# Port_Controller.net
KiCad netlist of a schematic drawn in Altium Designer
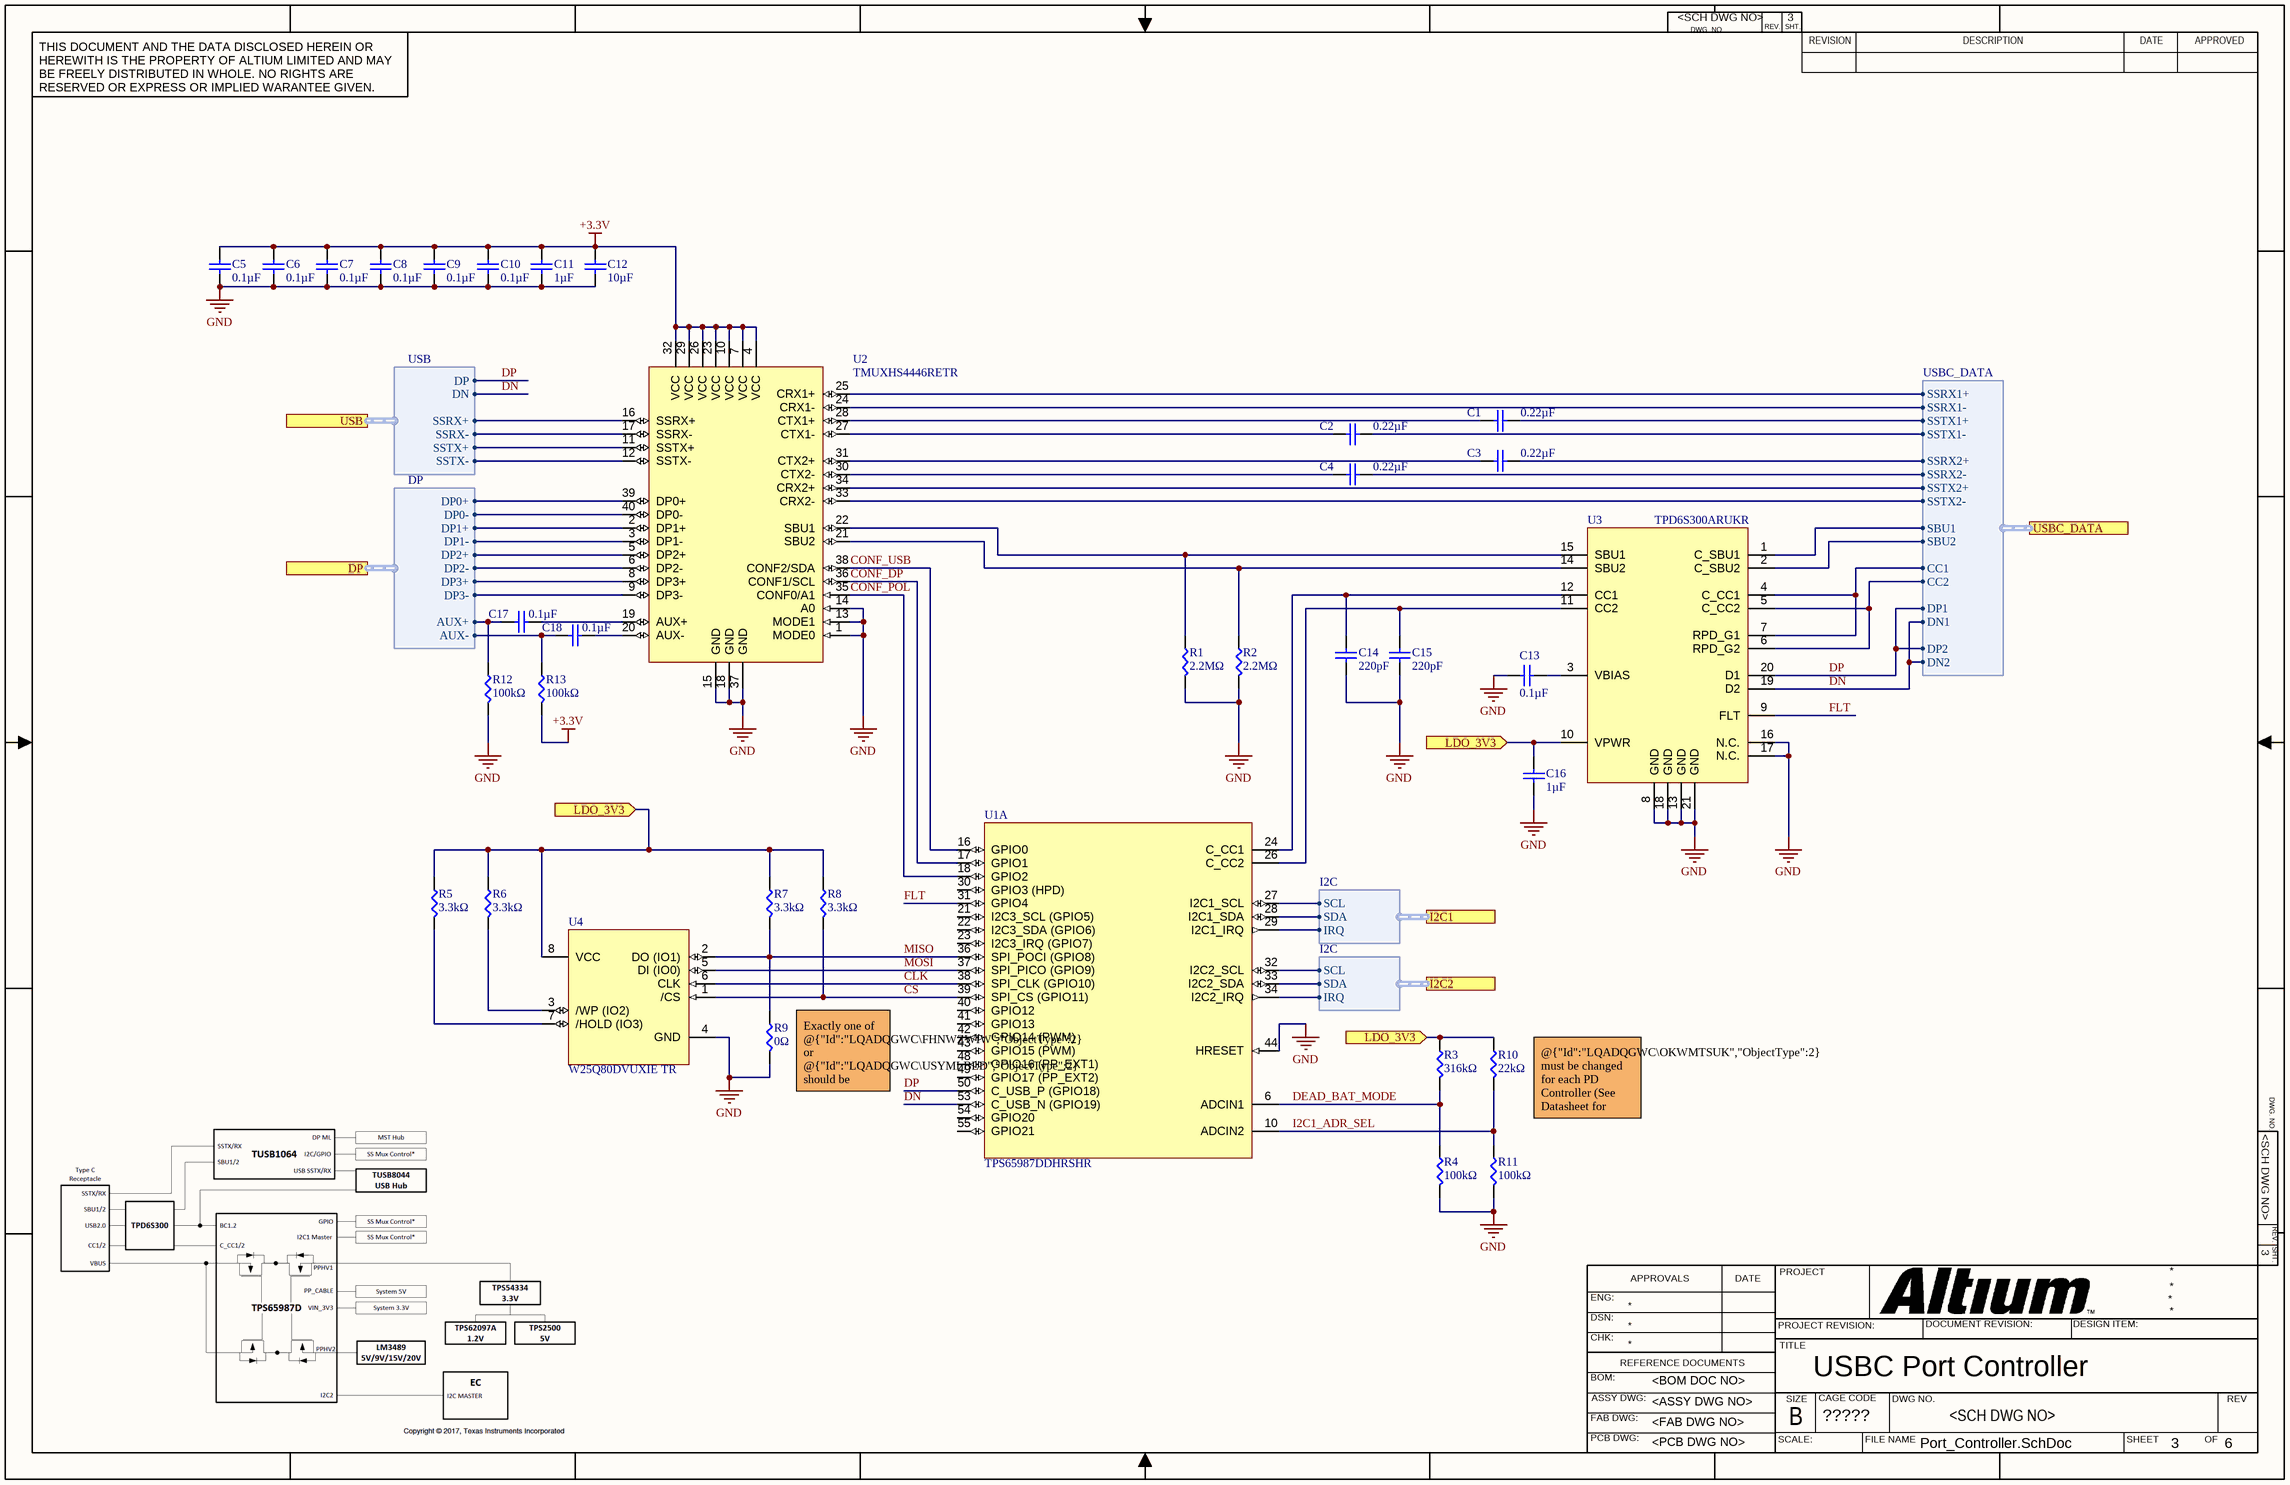
[diagram p0: Port_Controller.SchDoc]

(export (version "E")
  (design (tool "Eeschema 10.0.6"))
  (components
    (comp (ref "C1")
      (value "0.22µF")
      (footprint "CAP0402")
      (description "0.22 µF ±10% 50V Ceramic Capacitor X5R 0402 (1005 Metric)")
      (fields (field (name "VOLTAGE") "50V") (field (name "Comment") "UMK105BJ224KV-F"))
      (libsource (lib "Schlib1") (part "UMK105BJ224KV-F"))
    )
    (comp (ref "C2")
      (value "0.22µF")
      (footprint "CAP0402")
      (description "0.22 µF ±10% 50V Ceramic Capacitor X5R 0402 (1005 Metric)")
      (fields (field (name "VOLTAGE") "50V") (field (name "Comment") "UMK105BJ224KV-F"))
      (libsource (lib "Schlib1") (part "UMK105BJ224KV-F"))
    )
    (comp (ref "C3")
      (value "0.22µF")
      (footprint "CAP0402")
      (description "0.22 µF ±10% 50V Ceramic Capacitor X5R 0402 (1005 Metric)")
      (fields (field (name "VOLTAGE") "50V") (field (name "Comment") "UMK105BJ224KV-F"))
      (libsource (lib "Schlib1") (part "UMK105BJ224KV-F"))
    )
    (comp (ref "C4")
      (value "0.22µF")
      (footprint "CAP0402")
      (description "0.22 µF ±10% 50V Ceramic Capacitor X5R 0402 (1005 Metric)")
      (fields (field (name "VOLTAGE") "50V") (field (name "Comment") "UMK105BJ224KV-F"))
      (libsource (lib "Schlib1") (part "UMK105BJ224KV-F"))
    )
    (comp (ref "C5")
      (value "0.1µF")
      (footprint "CAP0402")
      (description "0.1 µF ±10% 50V Ceramic Capacitor X5R 0402 (1005 Metric)")
      (fields (field (name "VOLTAGE") "50V") (field (name "Comment") "CC0402KRX5R9BB104"))
      (libsource (lib "Schlib1") (part "CC0402KRX5R9BB104"))
    )
    (comp (ref "C6")
      (value "0.1µF")
      (footprint "CAP0402")
      (description "0.1 µF ±10% 50V Ceramic Capacitor X5R 0402 (1005 Metric)")
      (fields (field (name "VOLTAGE") "50V") (field (name "Comment") "CC0402KRX5R9BB104"))
      (libsource (lib "Schlib1") (part "CC0402KRX5R9BB104"))
    )
    (comp (ref "C7")
      (value "0.1µF")
      (footprint "CAP0402")
      (description "0.1 µF ±10% 50V Ceramic Capacitor X5R 0402 (1005 Metric)")
      (fields (field (name "VOLTAGE") "50V") (field (name "Comment") "CC0402KRX5R9BB104"))
      (libsource (lib "Schlib1") (part "CC0402KRX5R9BB104"))
    )
    (comp (ref "C8")
      (value "0.1µF")
      (footprint "CAP0402")
      (description "0.1 µF ±10% 50V Ceramic Capacitor X5R 0402 (1005 Metric)")
      (fields (field (name "VOLTAGE") "50V") (field (name "Comment") "CC0402KRX5R9BB104"))
      (libsource (lib "Schlib1") (part "CC0402KRX5R9BB104"))
    )
    (comp (ref "C9")
      (value "0.1µF")
      (footprint "CAP0402")
      (description "0.1 µF ±10% 50V Ceramic Capacitor X5R 0402 (1005 Metric)")
      (fields (field (name "VOLTAGE") "50V") (field (name "Comment") "CC0402KRX5R9BB104"))
      (libsource (lib "Schlib1") (part "CC0402KRX5R9BB104"))
    )
    (comp (ref "C10")
      (value "0.1µF")
      (footprint "CAP0402")
      (description "0.1 µF ±10% 50V Ceramic Capacitor X5R 0402 (1005 Metric)")
      (fields (field (name "VOLTAGE") "50V") (field (name "Comment") "CC0402KRX5R9BB104"))
      (libsource (lib "Schlib1") (part "CC0402KRX5R9BB104"))
    )
    (comp (ref "C11")
      (value "1µF")
      (footprint "CAP0402")
      (description "1 µF ±10% 50V Ceramic Capacitor X5R 0402 (1005 Metric)")
      (fields (field (name "VOLTAGE") "50V") (field (name "Comment") "GRM155R61H105KE05D"))
      (libsource (lib "Schlib1") (part "GRM155R61H105KE05D"))
    )
    (comp (ref "C12")
      (value "10µF")
      (footprint "CAP0402")
      (description "10 µF ±20% 6.3V Ceramic Capacitor X5R 0402 (1005 Metric)")
      (fields (field (name "VOLTAGE") "6.3V") (field (name "Comment") "CL05A106MQ5NUNC"))
      (libsource (lib "Schlib1") (part "CL05A106MQ5NUNC"))
    )
    (comp (ref "C13")
      (value "0.1µF")
      (footprint "CAP0402")
      (description "0.1 µF ±10% 50V Ceramic Capacitor X5R 0402 (1005 Metric)")
      (fields (field (name "VOLTAGE") "50V") (field (name "Comment") "CC0402KRX5R9BB104"))
      (libsource (lib "Schlib1") (part "CC0402KRX5R9BB104"))
    )
    (comp (ref "C14")
      (value "220pF")
      (footprint "CAP0402")
      (description "220 pF ±5% 50V Ceramic Capacitor C0G, NP0 0402 (1005 Metric)")
      (fields (field (name "VOLTAGE") "50V") (field (name "Comment") "GRM1555C1H221JA01D"))
      (libsource (lib "Schlib1") (part "GRM1555C1H221JA01D"))
    )
    (comp (ref "C15")
      (value "220pF")
      (footprint "CAP0402")
      (description "220 pF ±5% 50V Ceramic Capacitor C0G, NP0 0402 (1005 Metric)")
      (fields (field (name "VOLTAGE") "50V") (field (name "Comment") "GRM1555C1H221JA01D"))
      (libsource (lib "Schlib1") (part "GRM1555C1H221JA01D"))
    )
    (comp (ref "C16")
      (value "1µF")
      (footprint "CAP0402")
      (description "1 µF ±10% 50V Ceramic Capacitor X5R 0402 (1005 Metric)")
      (fields (field (name "VOLTAGE") "50V") (field (name "Comment") "GRM155R61H105KE05D"))
      (libsource (lib "Schlib1") (part "GRM155R61H105KE05D"))
    )
    (comp (ref "C17")
      (value "0.1µF")
      (footprint "CAP0402")
      (description "0.1 µF ±10% 50V Ceramic Capacitor X5R 0402 (1005 Metric)")
      (fields (field (name "VOLTAGE") "50V") (field (name "Comment") "CC0402KRX5R9BB104"))
      (libsource (lib "Schlib1") (part "CC0402KRX5R9BB104"))
    )
    (comp (ref "C18")
      (value "0.1µF")
      (footprint "CAP0402")
      (description "0.1 µF ±10% 50V Ceramic Capacitor X5R 0402 (1005 Metric)")
      (fields (field (name "VOLTAGE") "50V") (field (name "Comment") "CC0402KRX5R9BB104"))
      (libsource (lib "Schlib1") (part "CC0402KRX5R9BB104"))
    )
    (comp (ref "R1")
      (value "2.2MΩ")
      (footprint "RES0402")
      (description "2.2 MOhms ±1% 0.063W, 1/16W Chip Resistor 0402 (1005 Metric) Moisture Resistant Thick Film")
      (fields (field (name "Comment") "RC0402FR-072M2L"))
      (libsource (lib "Schlib1") (part "RC0402FR-072M2L"))
    )
    (comp (ref "R2")
      (value "2.2MΩ")
      (footprint "RES0402")
      (description "2.2 MOhms ±1% 0.063W, 1/16W Chip Resistor 0402 (1005 Metric) Moisture Resistant Thick Film")
      (fields (field (name "Comment") "RC0402FR-072M2L"))
      (libsource (lib "Schlib1") (part "RC0402FR-072M2L"))
    )
    (comp (ref "R3")
      (value "316kΩ")
      (footprint "RES0402")
      (description "316 kOhms ±1% 0.1W, 1/10W Chip Resistor 0402 (1005 Metric) Automotive AEC-Q200 Thick Film")
      (fields (field (name "Comment") "CRCW0402316KFKED"))
      (libsource (lib "Schlib1") (part "CRCW0402316KFKED"))
    )
    (comp (ref "R4")
      (value "100kΩ")
      (footprint "RES0402")
      (description "100 kOhms ±1% 0.1W, 1/10W Chip Resistor 0402 (1005 Metric) Automotive AEC-Q200 Thick Film")
      (fields (field (name "Comment") "ERJ-2RKF1003X"))
      (libsource (lib "Schlib1") (part "ERJ-2RKF1003X"))
    )
    (comp (ref "R5")
      (value "3.3kΩ")
      (footprint "RES0402")
      (description "3.3 kOhms ±0.1% 0.063W, 1/16W Chip Resistor 0402 (1005 Metric) Automotive AEC-Q200 Thin Film")
      (fields (field (name "Comment") "ERA-2AEB332X"))
      (libsource (lib "Schlib1") (part "ERA-2AEB332X"))
    )
    (comp (ref "R6")
      (value "3.3kΩ")
      (footprint "RES0402")
      (description "3.3 kOhms ±0.1% 0.063W, 1/16W Chip Resistor 0402 (1005 Metric) Automotive AEC-Q200 Thin Film")
      (fields (field (name "Comment") "ERA-2AEB332X"))
      (libsource (lib "Schlib1") (part "ERA-2AEB332X"))
    )
    (comp (ref "R7")
      (value "3.3kΩ")
      (footprint "RES0402")
      (description "3.3 kOhms ±0.1% 0.063W, 1/16W Chip Resistor 0402 (1005 Metric) Automotive AEC-Q200 Thin Film")
      (fields (field (name "Comment") "ERA-2AEB332X"))
      (libsource (lib "Schlib1") (part "ERA-2AEB332X"))
    )
    (comp (ref "R8")
      (value "3.3kΩ")
      (footprint "RES0402")
      (description "3.3 kOhms ±0.1% 0.063W, 1/16W Chip Resistor 0402 (1005 Metric) Automotive AEC-Q200 Thin Film")
      (fields (field (name "Comment") "ERA-2AEB332X"))
      (libsource (lib "Schlib1") (part "ERA-2AEB332X"))
    )
    (comp (ref "R9")
      (value "0Ω")
      (footprint "RES0402")
      (description "0 Ohms Jumper Chip Resistor 0402 (1005 Metric) Moisture Resistant Thick Film")
      (fields (field (name "Comment") "RC0402JR-070RL"))
      (libsource (lib "Schlib1") (part "RC0402JR-070RL"))
    )
    (comp (ref "R10")
      (value "22kΩ")
      (footprint "RES0402")
      (description "22 kOhms ±1% 0.1W, 1/10W Chip Resistor 0402 (1005 Metric) Automotive AEC-Q200 Thick Film")
      (fields (field (name "Comment") "ERJ-2RKF2202X"))
      (libsource (lib "Schlib1") (part "ERJ-2RKF2202X"))
    )
    (comp (ref "R11")
      (value "100kΩ")
      (footprint "RES0402")
      (description "100 kOhms ±1% 0.1W, 1/10W Chip Resistor 0402 (1005 Metric) Automotive AEC-Q200 Thick Film")
      (fields (field (name "Comment") "ERJ-2RKF1003X"))
      (libsource (lib "Schlib1") (part "ERJ-2RKF1003X"))
    )
    (comp (ref "R12")
      (value "100kΩ")
      (footprint "RES0402")
      (description "100 kOhms ±1% 0.1W, 1/10W Chip Resistor 0402 (1005 Metric) Automotive AEC-Q200 Thick Film")
      (fields (field (name "Comment") "ERJ-2RKF1003X"))
      (libsource (lib "Schlib1") (part "ERJ-2RKF1003X"))
    )
    (comp (ref "R13")
      (value "100kΩ")
      (footprint "RES0402")
      (description "100 kOhms ±1% 0.1W, 1/10W Chip Resistor 0402 (1005 Metric) Automotive AEC-Q200 Thick Film")
      (fields (field (name "Comment") "ERJ-2RKF1003X"))
      (libsource (lib "Schlib1") (part "ERJ-2RKF1003X"))
    )
    (comp (ref "U1")
      (value "TPS65987DDHRSHR")
      (footprint "56-VQFN (7x7)")
      (description "USB, Type-C Controller PMIC 56-VQFN (7x7)")
      (fields (field (name "MANUFACTURER") "Texas Instruments"))
      (libsource (lib "Schlib1") (part "TPS65987DDHRSHR"))
    )
    (comp (ref "U2")
      (value "TMUXHS4446RETR")
      (description "4 Circuit IC Switch 4:4 7Ohm (Typ) 40-WQFN (6x3)")
      (fields (field (name "MANUFACTURER") "Texas Instruments"))
      (libsource (lib "Schlib1") (part "TMUXHS4446RETR"))
    )
    (comp (ref "U3")
      (value "TPD6S300ARUKR")
      (description "Overvoltage/Surge Protection IC 8V Internal Switch 20-WQFN (3x3)")
      (fields (field (name "MANUFACTURER") "Texas Instruments"))
      (libsource (lib "Schlib1") (part "TPD6S300ARUKR"))
    )
    (comp (ref "U4")
      (value "W25Q80DVUXIE TR")
      (description "FLASH - NOR Memory IC 8Mbit SPI - Quad I/O 104 MHz 8-USON (2x3)")
      (fields (field (name "MANUFACTURER") "Winbond Electronics"))
      (libsource (lib "Schlib1") (part "W25Q80DVUXIE TR"))
    )
  )
  (nets
    (net (code "4") (name "+3.3V") (class "Default")
      (node (ref "C10") (pin "2") (pinfunction "2_2") (pintype "passive"))
      (node (ref "C11") (pin "2") (pinfunction "2_2") (pintype "passive"))
      (node (ref "C12") (pin "2") (pinfunction "2_2") (pintype "passive"))
      (node (ref "C5") (pin "2") (pinfunction "2_2") (pintype "passive"))
      (node (ref "C6") (pin "2") (pinfunction "2_2") (pintype "passive"))
      (node (ref "C7") (pin "2") (pinfunction "2_2") (pintype "passive"))
      (node (ref "C8") (pin "2") (pinfunction "2_2") (pintype "passive"))
      (node (ref "C9") (pin "2") (pinfunction "2_2") (pintype "passive"))
      (node (ref "R13") (pin "1") (pinfunction "1_1") (pintype "passive"))
      (node (ref "U2") (pin "10") (pinfunction "VCC_10") (pintype "passive"))
      (node (ref "U2") (pin "23") (pinfunction "VCC_23") (pintype "passive"))
      (node (ref "U2") (pin "26") (pinfunction "VCC_26") (pintype "passive"))
      (node (ref "U2") (pin "29") (pinfunction "VCC_29") (pintype "passive"))
      (node (ref "U2") (pin "32") (pinfunction "VCC_32") (pintype "passive"))
      (node (ref "U2") (pin "4") (pinfunction "VCC_4") (pintype "passive"))
      (node (ref "U2") (pin "7") (pinfunction "VCC_7") (pintype "passive"))
    )
    (net (code "5") (name "/AUX+") (class "Default")
      (node (ref "C17") (pin "1") (pinfunction "1_1") (pintype "passive"))
      (node (ref "R12") (pin "2") (pinfunction "2_2") (pintype "passive"))
    )
    (net (code "6") (name "/AUX-") (class "Default")
      (node (ref "C18") (pin "1") (pinfunction "1_1") (pintype "passive"))
      (node (ref "R13") (pin "2") (pinfunction "2_2") (pintype "passive"))
    )
    (net (code "7") (name "/CC1") (class "Default")
      (node (ref "U3") (pin "4") (pinfunction "C_CC1_4") (pintype "passive"))
      (node (ref "U3") (pin "7") (pinfunction "RPD_G1_7") (pintype "passive"))
    )
    (net (code "8") (name "/CC2") (class "Default")
      (node (ref "U3") (pin "5") (pinfunction "C_CC2_5") (pintype "passive"))
      (node (ref "U3") (pin "6") (pinfunction "RPD_G2_6") (pintype "passive"))
    )
    (net (code "9") (name "/CLK") (class "Default")
      (node (ref "U1") (pin "38") (pinfunction "SPI_CLK_(GPIO10)_38") (pintype "bidirectional"))
      (node (ref "U4") (pin "6") (pinfunction "CLK_6") (pintype "input"))
    )
    (net (code "10") (name "/CONF_DP") (class "Default")
      (node (ref "U1") (pin "17") (pinfunction "GPIO1_17") (pintype "bidirectional"))
      (node (ref "U2") (pin "36") (pinfunction "CONF1/SCL_36") (pintype "bidirectional"))
    )
    (net (code "11") (name "/CONF_POL") (class "Default")
      (node (ref "U1") (pin "18") (pinfunction "GPIO2_18") (pintype "bidirectional"))
      (node (ref "U2") (pin "35") (pinfunction "CONF0/A1_35") (pintype "input"))
    )
    (net (code "12") (name "/CONF_USB") (class "Default")
      (node (ref "U1") (pin "16") (pinfunction "GPIO0_16") (pintype "bidirectional"))
      (node (ref "U2") (pin "38") (pinfunction "CONF2/SDA_38") (pintype "bidirectional"))
    )
    (net (code "13") (name "/CS") (class "Default")
      (node (ref "R8") (pin "1") (pinfunction "1_1") (pintype "passive"))
      (node (ref "U1") (pin "39") (pinfunction "SPI_CS_(GPIO11)_39") (pintype "bidirectional"))
      (node (ref "U4") (pin "1") (pinfunction "/CS_1") (pintype "input"))
    )
    (net (code "14") (name "/DEAD_BAT_MODE") (class "Default")
      (node (ref "R3") (pin "1") (pinfunction "1_1") (pintype "passive"))
      (node (ref "R4") (pin "2") (pinfunction "2_2") (pintype "passive"))
      (node (ref "U1") (pin "6") (pinfunction "ADCIN1_6") (pintype "passive"))
    )
    (net (code "15") (name "/DN") (class "Default")
      (node (ref "U1") (pin "53") (pinfunction "C_USB_N_(GPIO19)_53") (pintype "bidirectional"))
      (node (ref "U3") (pin "19") (pinfunction "D2_19") (pintype "passive"))
    )
    (net (code "16") (name "/DP") (class "Default")
      (node (ref "U1") (pin "50") (pinfunction "C_USB_P_(GPIO18)_50") (pintype "bidirectional"))
      (node (ref "U3") (pin "20") (pinfunction "D1_20") (pintype "passive"))
    )
    (net (code "17") (name "/DP0+") (class "Default")
      (node (ref "U2") (pin "39") (pinfunction "DP0+_39") (pintype "bidirectional"))
    )
    (net (code "18") (name "/DP0-") (class "Default")
      (node (ref "U2") (pin "40") (pinfunction "DP0-_40") (pintype "bidirectional"))
    )
    (net (code "19") (name "/DP1+") (class "Default")
      (node (ref "U2") (pin "2") (pinfunction "DP1+_2") (pintype "bidirectional"))
    )
    (net (code "20") (name "/DP1-") (class "Default")
      (node (ref "U2") (pin "3") (pinfunction "DP1-_3") (pintype "bidirectional"))
    )
    (net (code "21") (name "/DP2+") (class "Default")
      (node (ref "U2") (pin "5") (pinfunction "DP2+_5") (pintype "bidirectional"))
    )
    (net (code "22") (name "/DP2-") (class "Default")
      (node (ref "U2") (pin "6") (pinfunction "DP2-_6") (pintype "bidirectional"))
    )
    (net (code "23") (name "/DP3+") (class "Default")
      (node (ref "U2") (pin "8") (pinfunction "DP3+_8") (pintype "bidirectional"))
    )
    (net (code "24") (name "/DP3-") (class "Default")
      (node (ref "U2") (pin "9") (pinfunction "DP3-_9") (pintype "bidirectional"))
    )
    (net (code "25") (name "/FLT") (class "Default")
      (node (ref "U1") (pin "31") (pinfunction "GPIO4_31") (pintype "bidirectional"))
      (node (ref "U3") (pin "9") (pinfunction "FLT_9") (pintype "passive"))
    )
    (net (code "26") (name "/I2C1_ADR_SEL") (class "Default")
      (node (ref "R10") (pin "1") (pinfunction "1_1") (pintype "passive"))
      (node (ref "R11") (pin "2") (pinfunction "2_2") (pintype "passive"))
      (node (ref "U1") (pin "10") (pinfunction "ADCIN2_10") (pintype "passive"))
    )
    (net (code "27") (name "/LDO_3V3") (class "Default")
      (node (ref "C16") (pin "2") (pinfunction "2_2") (pintype "passive"))
      (node (ref "R10") (pin "2") (pinfunction "2_2") (pintype "passive"))
      (node (ref "R3") (pin "2") (pinfunction "2_2") (pintype "passive"))
      (node (ref "R5") (pin "2") (pinfunction "2_2") (pintype "passive"))
      (node (ref "R6") (pin "2") (pinfunction "2_2") (pintype "passive"))
      (node (ref "R7") (pin "2") (pinfunction "2_2") (pintype "passive"))
      (node (ref "R8") (pin "2") (pinfunction "2_2") (pintype "passive"))
      (node (ref "U3") (pin "10") (pinfunction "VPWR_10") (pintype "passive"))
      (node (ref "U4") (pin "8") (pinfunction "VCC_8") (pintype "passive"))
    )
    (net (code "28") (name "/MISO") (class "Default")
      (node (ref "R7") (pin "1") (pinfunction "1_1") (pintype "passive"))
      (node (ref "R9") (pin "2") (pinfunction "2_2") (pintype "passive"))
      (node (ref "U1") (pin "36") (pinfunction "SPI_POCI_(GPIO8)_36") (pintype "bidirectional"))
      (node (ref "U4") (pin "2") (pinfunction "DO_(IO1)_2") (pintype "bidirectional"))
    )
    (net (code "29") (name "/MOSI") (class "Default")
      (node (ref "U1") (pin "37") (pinfunction "SPI_PICO_(GPIO9)_37") (pintype "bidirectional"))
      (node (ref "U4") (pin "5") (pinfunction "DI_(IO0)_5") (pintype "bidirectional"))
    )
    (net (code "30") (name "/SBU1") (class "Default")
      (node (ref "U3") (pin "1") (pinfunction "C_SBU1_1") (pintype "passive"))
    )
    (net (code "31") (name "/SBU2") (class "Default")
      (node (ref "U3") (pin "2") (pinfunction "C_SBU2_2") (pintype "passive"))
    )
    (net (code "32") (name "/SSRX+") (class "Default")
      (node (ref "U2") (pin "16") (pinfunction "SSRX+_16") (pintype "bidirectional"))
    )
    (net (code "33") (name "/SSRX-") (class "Default")
      (node (ref "U2") (pin "17") (pinfunction "SSRX-_17") (pintype "bidirectional"))
    )
    (net (code "34") (name "/SSRX1+") (class "Default")
      (node (ref "U2") (pin "25") (pinfunction "CRX1+_25") (pintype "bidirectional"))
    )
    (net (code "35") (name "/SSRX1-") (class "Default")
      (node (ref "U2") (pin "24") (pinfunction "CRX1-_24") (pintype "bidirectional"))
    )
    (net (code "36") (name "/SSRX2+") (class "Default")
      (node (ref "C3") (pin "2") (pinfunction "2_2") (pintype "passive"))
    )
    (net (code "37") (name "/SSRX2-") (class "Default")
      (node (ref "C4") (pin "2") (pinfunction "2_2") (pintype "passive"))
    )
    (net (code "38") (name "/SSTX+") (class "Default")
      (node (ref "U2") (pin "11") (pinfunction "SSTX+_11") (pintype "bidirectional"))
    )
    (net (code "39") (name "/SSTX-") (class "Default")
      (node (ref "U2") (pin "12") (pinfunction "SSTX-_12") (pintype "bidirectional"))
    )
    (net (code "40") (name "/SSTX1+") (class "Default")
      (node (ref "C1") (pin "2") (pinfunction "2_2") (pintype "passive"))
    )
    (net (code "41") (name "/SSTX1-") (class "Default")
      (node (ref "C2") (pin "2") (pinfunction "2_2") (pintype "passive"))
    )
    (net (code "42") (name "/SSTX2+") (class "Default")
      (node (ref "U2") (pin "34") (pinfunction "CRX2+_34") (pintype "bidirectional"))
    )
    (net (code "43") (name "/SSTX2-") (class "Default")
      (node (ref "U2") (pin "33") (pinfunction "CRX2-_33") (pintype "bidirectional"))
    )
    (net (code "48") (name "GND") (class "Default")
      (node (ref "C10") (pin "1") (pinfunction "1_1") (pintype "passive"))
      (node (ref "C11") (pin "1") (pinfunction "1_1") (pintype "passive"))
      (node (ref "C12") (pin "1") (pinfunction "1_1") (pintype "passive"))
      (node (ref "C13") (pin "1") (pinfunction "1_1") (pintype "passive"))
      (node (ref "C14") (pin "1") (pinfunction "1_1") (pintype "passive"))
      (node (ref "C15") (pin "1") (pinfunction "1_1") (pintype "passive"))
      (node (ref "C16") (pin "1") (pinfunction "1_1") (pintype "passive"))
      (node (ref "C5") (pin "1") (pinfunction "1_1") (pintype "passive"))
      (node (ref "C6") (pin "1") (pinfunction "1_1") (pintype "passive"))
      (node (ref "C7") (pin "1") (pinfunction "1_1") (pintype "passive"))
      (node (ref "C8") (pin "1") (pinfunction "1_1") (pintype "passive"))
      (node (ref "C9") (pin "1") (pinfunction "1_1") (pintype "passive"))
      (node (ref "R1") (pin "1") (pinfunction "1_1") (pintype "passive"))
      (node (ref "R11") (pin "1") (pinfunction "1_1") (pintype "passive"))
      (node (ref "R12") (pin "1") (pinfunction "1_1") (pintype "passive"))
      (node (ref "R2") (pin "1") (pinfunction "1_1") (pintype "passive"))
      (node (ref "R4") (pin "1") (pinfunction "1_1") (pintype "passive"))
      (node (ref "R9") (pin "1") (pinfunction "1_1") (pintype "passive"))
      (node (ref "U1") (pin "44") (pinfunction "HRESET_44") (pintype "input"))
      (node (ref "U2") (pin "1") (pinfunction "MODE0_1") (pintype "input"))
      (node (ref "U2") (pin "13") (pinfunction "MODE1_13") (pintype "input"))
      (node (ref "U2") (pin "14") (pinfunction "A0_14") (pintype "input"))
      (node (ref "U2") (pin "15") (pinfunction "GND_15") (pintype "passive"))
      (node (ref "U2") (pin "18") (pinfunction "GND_18") (pintype "passive"))
      (node (ref "U2") (pin "37") (pinfunction "GND_37") (pintype "passive"))
      (node (ref "U3") (pin "13") (pinfunction "GND_13") (pintype "passive"))
      (node (ref "U3") (pin "16") (pinfunction "N.C._16") (pintype "passive"))
      (node (ref "U3") (pin "17") (pinfunction "N.C._17") (pintype "passive"))
      (node (ref "U3") (pin "18") (pinfunction "GND_18") (pintype "passive"))
      (node (ref "U3") (pin "21") (pinfunction "GND_21") (pintype "passive"))
      (node (ref "U3") (pin "8") (pinfunction "GND_8") (pintype "passive"))
      (node (ref "U4") (pin "4") (pinfunction "GND_4") (pintype "passive"))
    )
    (net (code "49") (name "Net-(U1A-C_CC1)") (class "Default")
      (node (ref "C14") (pin "2") (pinfunction "2_2") (pintype "passive"))
      (node (ref "U1") (pin "24") (pinfunction "C_CC1_24") (pintype "passive"))
      (node (ref "U3") (pin "12") (pinfunction "CC1_12") (pintype "passive"))
    )
    (net (code "50") (name "Net-(U1A-C_CC2)") (class "Default")
      (node (ref "C15") (pin "2") (pinfunction "2_2") (pintype "passive"))
      (node (ref "U1") (pin "26") (pinfunction "C_CC2_26") (pintype "passive"))
      (node (ref "U3") (pin "11") (pinfunction "CC2_11") (pintype "passive"))
    )
    (net (code "51") (name "Net-(U2-AUX+)") (class "Default")
      (node (ref "C17") (pin "2") (pinfunction "2_2") (pintype "passive"))
      (node (ref "U2") (pin "19") (pinfunction "AUX+_19") (pintype "bidirectional"))
    )
    (net (code "52") (name "Net-(U2-AUX-)") (class "Default")
      (node (ref "C18") (pin "2") (pinfunction "2_2") (pintype "passive"))
      (node (ref "U2") (pin "20") (pinfunction "AUX-_20") (pintype "bidirectional"))
    )
    (net (code "53") (name "Net-(U2-CTX1+)") (class "Default")
      (node (ref "C1") (pin "1") (pinfunction "1_1") (pintype "passive"))
      (node (ref "U2") (pin "28") (pinfunction "CTX1+_28") (pintype "bidirectional"))
    )
    (net (code "54") (name "Net-(U2-CTX1-)") (class "Default")
      (node (ref "C2") (pin "1") (pinfunction "1_1") (pintype "passive"))
      (node (ref "U2") (pin "27") (pinfunction "CTX1-_27") (pintype "bidirectional"))
    )
    (net (code "55") (name "Net-(U2-CTX2+)") (class "Default")
      (node (ref "C3") (pin "1") (pinfunction "1_1") (pintype "passive"))
      (node (ref "U2") (pin "31") (pinfunction "CTX2+_31") (pintype "bidirectional"))
    )
    (net (code "56") (name "Net-(U2-CTX2-)") (class "Default")
      (node (ref "C4") (pin "1") (pinfunction "1_1") (pintype "passive"))
      (node (ref "U2") (pin "30") (pinfunction "CTX2-_30") (pintype "bidirectional"))
    )
    (net (code "57") (name "Net-(U2-SBU1)") (class "Default")
      (node (ref "R1") (pin "2") (pinfunction "2_2") (pintype "passive"))
      (node (ref "U2") (pin "22") (pinfunction "SBU1_22") (pintype "bidirectional"))
      (node (ref "U3") (pin "15") (pinfunction "SBU1_15") (pintype "passive"))
    )
    (net (code "58") (name "Net-(U2-SBU2)") (class "Default")
      (node (ref "R2") (pin "2") (pinfunction "2_2") (pintype "passive"))
      (node (ref "U2") (pin "21") (pinfunction "SBU2_21") (pintype "bidirectional"))
      (node (ref "U3") (pin "14") (pinfunction "SBU2_14") (pintype "passive"))
    )
    (net (code "59") (name "Net-(U3-VBIAS)") (class "Default")
      (node (ref "C13") (pin "2") (pinfunction "2_2") (pintype "passive"))
      (node (ref "U3") (pin "3") (pinfunction "VBIAS_3") (pintype "passive"))
    )
    (net (code "60") (name "Net-(U4-{slash}HOLD_(IO3))") (class "Default")
      (node (ref "R5") (pin "1") (pinfunction "1_1") (pintype "passive"))
      (node (ref "U4") (pin "7") (pinfunction "/HOLD_(IO3)_7") (pintype "bidirectional"))
    )
    (net (code "61") (name "Net-(U4-{slash}WP_(IO2))") (class "Default")
      (node (ref "R6") (pin "1") (pinfunction "1_1") (pintype "passive"))
      (node (ref "U4") (pin "3") (pinfunction "/WP_(IO2)_3") (pintype "bidirectional"))
    )
    (net (code "62") (name "unconnected-(U1A-GPIO3_(HPD)-Pad30)") (class "Default")
      (node (ref "U1") (pin "30") (pinfunction "GPIO3_(HPD)_30") (pintype "bidirectional"))
    )
    (net (code "63") (name "unconnected-(U1A-GPIO12-Pad40)") (class "Default")
      (node (ref "U1") (pin "40") (pinfunction "GPIO12_40") (pintype "bidirectional"))
    )
    (net (code "64") (name "unconnected-(U1A-GPIO13-Pad41)") (class "Default")
      (node (ref "U1") (pin "41") (pinfunction "GPIO13_41") (pintype "bidirectional"))
    )
    (net (code "65") (name "unconnected-(U1A-GPIO14_(PWM)-Pad42)") (class "Default")
      (node (ref "U1") (pin "42") (pinfunction "GPIO14_(PWM)_42") (pintype "bidirectional"))
    )
    (net (code "66") (name "unconnected-(U1A-GPIO15_(PWM)-Pad43)") (class "Default")
      (node (ref "U1") (pin "43") (pinfunction "GPIO15_(PWM)_43") (pintype "bidirectional"))
    )
    (net (code "67") (name "unconnected-(U1A-GPIO16_(PP_EXT1)-Pad48)") (class "Default")
      (node (ref "U1") (pin "48") (pinfunction "GPIO16_(PP_EXT1)_48") (pintype "bidirectional"))
    )
    (net (code "68") (name "unconnected-(U1A-GPIO17_(PP_EXT2)-Pad49)") (class "Default")
      (node (ref "U1") (pin "49") (pinfunction "GPIO17_(PP_EXT2)_49") (pintype "bidirectional"))
    )
    (net (code "69") (name "unconnected-(U1A-GPIO20-Pad54)") (class "Default")
      (node (ref "U1") (pin "54") (pinfunction "GPIO20_54") (pintype "bidirectional"))
    )
    (net (code "70") (name "unconnected-(U1A-GPIO21-Pad55)") (class "Default")
      (node (ref "U1") (pin "55") (pinfunction "GPIO21_55") (pintype "bidirectional"))
    )
    (net (code "71") (name "unconnected-(U1A-I2C1_IRQ-Pad29)") (class "Default")
      (node (ref "U1") (pin "29") (pinfunction "I2C1_IRQ_29") (pintype "output"))
    )
    (net (code "72") (name "unconnected-(U1A-I2C1_SCL-Pad27)") (class "Default")
      (node (ref "U1") (pin "27") (pinfunction "I2C1_SCL_27") (pintype "bidirectional"))
    )
    (net (code "73") (name "unconnected-(U1A-I2C1_SDA-Pad28)") (class "Default")
      (node (ref "U1") (pin "28") (pinfunction "I2C1_SDA_28") (pintype "bidirectional"))
    )
    (net (code "74") (name "unconnected-(U1A-I2C2_IRQ-Pad34)") (class "Default")
      (node (ref "U1") (pin "34") (pinfunction "I2C2_IRQ_34") (pintype "output"))
    )
    (net (code "75") (name "unconnected-(U1A-I2C2_SCL-Pad32)") (class "Default")
      (node (ref "U1") (pin "32") (pinfunction "I2C2_SCL_32") (pintype "bidirectional"))
    )
    (net (code "76") (name "unconnected-(U1A-I2C2_SDA-Pad33)") (class "Default")
      (node (ref "U1") (pin "33") (pinfunction "I2C2_SDA_33") (pintype "bidirectional"))
    )
    (net (code "77") (name "unconnected-(U1A-I2C3_IRQ_(GPIO7)-Pad23)") (class "Default")
      (node (ref "U1") (pin "23") (pinfunction "I2C3_IRQ_(GPIO7)_23") (pintype "bidirectional"))
    )
    (net (code "78") (name "unconnected-(U1A-I2C3_SCL_(GPIO5)-Pad21)") (class "Default")
      (node (ref "U1") (pin "21") (pinfunction "I2C3_SCL_(GPIO5)_21") (pintype "bidirectional"))
    )
    (net (code "79") (name "unconnected-(U1A-I2C3_SDA_(GPIO6)-Pad22)") (class "Default")
      (node (ref "U1") (pin "22") (pinfunction "I2C3_SDA_(GPIO6)_22") (pintype "bidirectional"))
    )
  )
)
